# EasyEDApro.net
KiCad netlist of a schematic drawn in EasyEDA Pro
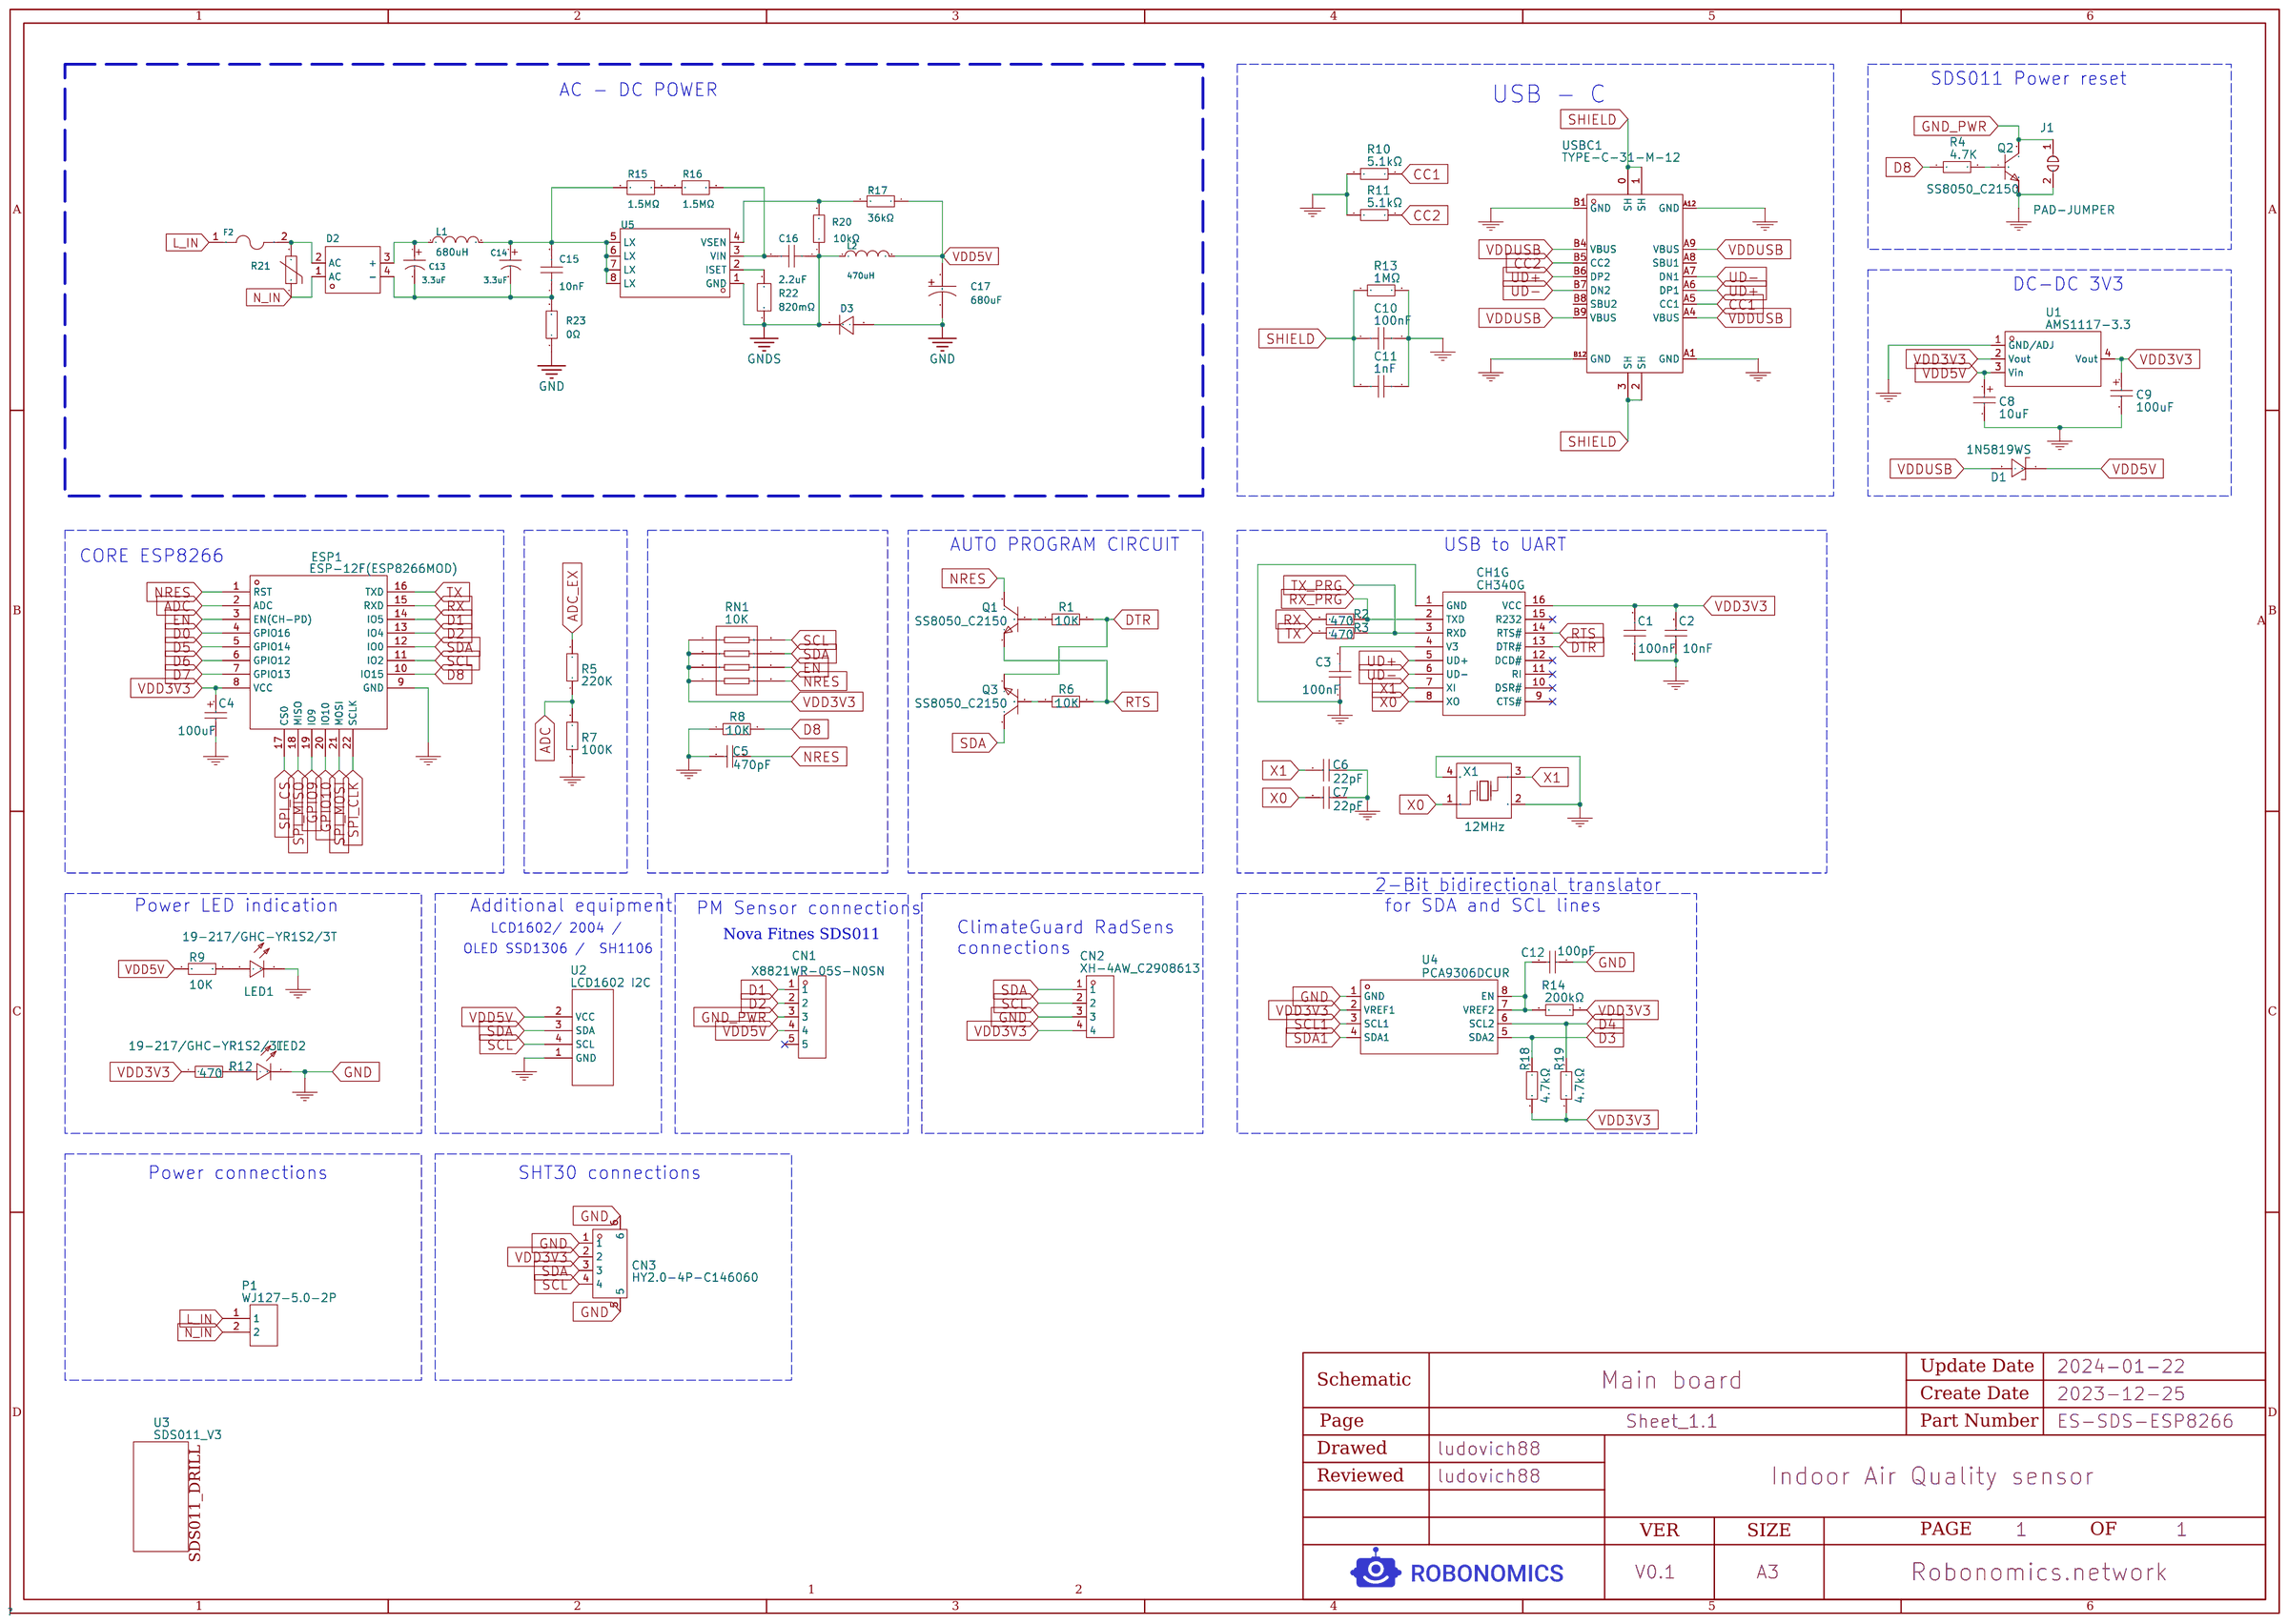
[diagram p0: schematic sheet]

(export (version "E")
  (design (tool "Eeschema 10.0.6"))
  (components
    (comp (ref "C1")
      (value "100nF")
      (footprint "easyedapro:C0603")
      (fields (field (name "Manufacturer Part") "CC0603KRX7R9BB104") (field (name "Manufacturer") "YAGEO"))
      (libsource (lib "easyedapro") (part "100nF"))
    )
    (comp (ref "C2")
      (value "10nF")
      (footprint "easyedapro:C0603")
      (fields (field (name "Manufacturer Part") "0603B103K500NT") (field (name "Manufacturer") "FH"))
      (libsource (lib "easyedapro") (part "10nF"))
    )
    (comp (ref "C3")
      (value "100nF")
      (footprint "easyedapro:C0603")
      (fields (field (name "Manufacturer Part") "CC0603KRX7R9BB104") (field (name "Manufacturer") "YAGEO"))
      (libsource (lib "easyedapro") (part "100nF"))
    )
    (comp (ref "C4")
      (value "100uF")
      (footprint "easyedapro:CAP-SMD_L3.5-W2.8")
      (fields (field (name "Manufacturer Part") "TAJB107K006RNJ") (field (name "Manufacturer") "AVX"))
      (libsource (lib "easyedapro") (part "100uF"))
    )
    (comp (ref "C5")
      (value "470pF")
      (footprint "easyedapro:C0603")
      (fields (field (name "Manufacturer Part") "0603B471K500NT") (field (name "Manufacturer") "FH"))
      (libsource (lib "easyedapro") (part "470pF"))
    )
    (comp (ref "C6")
      (value "22pF")
      (footprint "easyedapro:C0603")
      (fields (field (name "Manufacturer Part") "CL10C220JB8NNNC") (field (name "Manufacturer") "SAMSUNG"))
      (libsource (lib "easyedapro") (part "22pF"))
    )
    (comp (ref "C7")
      (value "22pF")
      (footprint "easyedapro:C0603")
      (fields (field (name "Manufacturer Part") "CL10C220JB8NNNC") (field (name "Manufacturer") "SAMSUNG"))
      (libsource (lib "easyedapro") (part "22pF"))
    )
    (comp (ref "C8")
      (value "10uF")
      (footprint "easyedapro:CAP-SMD_L3.2-W1.6-R-RD")
      (fields (field (name "Manufacturer Part") "CA45-A010M106T") (field (name "Manufacturer") "Xiangyee"))
      (libsource (lib "easyedapro") (part "10uF"))
    )
    (comp (ref "C9")
      (value "100uF")
      (footprint "easyedapro:CAP-SMD_L3.5-W2.8")
      (fields (field (name "Manufacturer Part") "TAJB107K006RNJ") (field (name "Manufacturer") "AVX"))
      (libsource (lib "easyedapro") (part "100uF"))
    )
    (comp (ref "C10")
      (value "100nF")
      (footprint "easyedapro:C0603")
      (fields (field (name "Manufacturer Part") "CC0603KRX7R9BB104") (field (name "Manufacturer") "YAGEO"))
      (libsource (lib "easyedapro") (part "100nF"))
    )
    (comp (ref "C11")
      (value "1nF")
      (footprint "easyedapro:C0603")
      (fields
        (field (name "Manufacturer Part") "GRM1885C1H102FA01D")
        (field (name "Manufacturer") "muRata(村田)")
      )
      (libsource (lib "easyedapro") (part "1nF"))
    )
    (comp (ref "C12")
      (value "100pF")
      (footprint "easyedapro:C0603")
      (fields (field (name "Manufacturer Part") "CL10C101JB8NNNC") (field (name "Manufacturer") "SAMSUNG"))
      (libsource (lib "easyedapro") (part "100pF"))
    )
    (comp (ref "C13")
      (value "3.3uF")
      (footprint "easyedapro:CAP-SMD_BD8.0-L8.3-W8.3-FD")
      (fields (field (name "Manufacturer Part") "UV2G3R3M0810") (field (name "Manufacturer") "HONOR(荣誉)"))
      (libsource (lib "easyedapro") (part "UV2G3R3M0810"))
    )
    (comp (ref "C14")
      (value "3.3uF")
      (footprint "easyedapro:CAP-SMD_BD8.0-L8.3-W8.3-FD")
      (fields (field (name "Manufacturer Part") "UV2G3R3M0810") (field (name "Manufacturer") "HONOR(荣誉)"))
      (libsource (lib "easyedapro") (part "UV2G3R3M0810"))
    )
    (comp (ref "C15")
      (value "10nF")
      (footprint "easyedapro:C1206")
      (fields (field (name "Manufacturer Part") "1206B103K102CT") (field (name "Manufacturer") "Walsin(华新科)"))
      (libsource (lib "easyedapro") (part "1206B103K102"))
    )
    (comp (ref "C16")
      (value "2.2uF")
      (footprint "easyedapro:C0805")
      (fields
        (field (name "Manufacturer Part") "CL21A225KBQNNNE")
        (field (name "Manufacturer") "SAMSUNG(三星)")
      )
      (libsource (lib "easyedapro") (part "CL21A225KBQNNNE"))
    )
    (comp (ref "C17")
      (value "680uF")
      (footprint "easyedapro:CAP-SMD_L7.3-W4.3")
      (fields (field (name "Manufacturer Part") "TAJE687K006RNJ") (field (name "Manufacturer") "KyoceraAVX"))
      (libsource (lib "easyedapro") (part "TAJE687K006RNJ"))
    )
    (comp (ref "CH1G")
      (value "CH340G")
      (footprint "easyedapro:SOIC-16_150MIL")
      (fields (field (name "Manufacturer") "WCH"))
      (libsource (lib "easyedapro") (part "CH340G"))
    )
    (comp (ref "CN1")
      (value "X8821WR-05S-N0SN")
      (footprint "easyedapro:CONN-TH_5P-P2.50_X8821WR-05S-N0SN")
      (fields (field (name "Manufacturer") "XKBConnectivity(中国星坤)"))
      (libsource (lib "easyedapro") (part "X8821WR-05S-N0SN"))
    )
    (comp (ref "CN2")
      (value "XH-4AW_C2908613")
      (footprint "easyedapro:CONN-TH_XH-4AW")
      (fields (field (name "Manufacturer Part") "XH-4AW") (field (name "Manufacturer") "HCTL(华灿天禄)"))
      (libsource (lib "easyedapro") (part "XH-4AW_C2908613"))
    )
    (comp (ref "CN3")
      (value "HY2.0-4P-C146060")
      (footprint "easyedapro:CONN-SMD_HY2.0-4P")
      (fields (field (name "Manufacturer Part") "HY-4P卧贴") (field (name "Manufacturer") "BOOMELE(博穆精密)"))
      (libsource (lib "easyedapro") (part "HY2.0-4P-C146060"))
    )
    (comp (ref "D1")
      (value "1N5819WS")
      (footprint "easyedapro:SOD-323_L1.8-W1.3-LS2.5-RD")
      (fields (field (name "Manufacturer") "GuangdongHottech"))
      (libsource (lib "easyedapro") (part "1N5819WS"))
    )
    (comp (ref "D2")
      (value "MB10F")
      (footprint "easyedapro:MBF_L4.8-W3.9-P2.50-LS6.7-BL")
      (fields (field (name "Manufacturer") "BORN(伯恩半导体)"))
      (libsource (lib "easyedapro") (part "MB10F_C306850"))
    )
    (comp (ref "D3")
      (value "ES1J")
      (footprint "easyedapro:SMA_L4.3-W2.6-LS5.2-RD")
      (fields (field (name "Manufacturer") "晶导微电子"))
      (libsource (lib "easyedapro") (part "ES1J_C115404"))
    )
    (comp (ref "ESP1")
      (value "ESP-12F(ESP8266MOD)")
      (footprint "easyedapro:WIFIM-SMD_ESP-12F-ESP8266MOD")
      (fields (field (name "Manufacturer") "Ai-Thinker"))
      (libsource (lib "easyedapro") (part "ESP-12F(ESP8266MOD)"))
    )
    (comp (ref "F2")
      (value "JFC2410-1200FS")
      (footprint "easyedapro:F2410")
      (fields (field (name "Manufacturer") "JDTfuse(集电通)"))
      (libsource (lib "easyedapro") (part "JFC2410-1200FS"))
    )
    (comp (ref "J1")
      (value "PAD-JUMPER")
      (footprint "easyedapro:PAD-JUMPER-2_1")
      (libsource (lib "easyedapro") (part "PAD-JUMPER"))
    )
    (comp (ref "L1")
      (value "680uH")
      (footprint "easyedapro:IND-SMD_L6.0-W6.0")
      (fields (field (name "Manufacturer Part") "YNR6045-681M") (field (name "Manufacturer") "YJYCOIN(益嘉源)"))
      (libsource (lib "easyedapro") (part "YNR6045-681M"))
    )
    (comp (ref "L2")
      (value "470uH")
      (footprint "easyedapro:IND-SMD_L4.0-W4.0")
      (fields (field (name "Manufacturer Part") "PNLS4030-471") (field (name "Manufacturer") "DMBJ(振宝佳)"))
      (libsource (lib "easyedapro") (part "PNLS4030-471"))
    )
    (comp (ref "LED1")
      (value "19-217/GHC-YR1S2/3T")
      (footprint "easyedapro:LED0603-R-RD")
      (fields (field (name "Manufacturer") "EVERLIGHT"))
      (libsource (lib "easyedapro") (part "19-217/GHC-YR1S2/3T"))
    )
    (comp (ref "LED2")
      (value "19-217/GHC-YR1S2/3T")
      (footprint "easyedapro:LED0603-R-RD")
      (fields (field (name "Manufacturer") "EVERLIGHT"))
      (libsource (lib "easyedapro") (part "19-217/GHC-YR1S2/3T"))
    )
    (comp (ref "P1")
      (value "WJ127-5.0-2P")
      (footprint "easyedapro:CONN-TH_2P-P5.00_CPC3703CTR")
      (fields (field (name "Manufacturer") "KANGNEX(康奈克斯电气)"))
      (libsource (lib "easyedapro") (part "WJ127-5.0-2P"))
    )
    (comp (ref "Q1")
      (value "SS8050_C2150")
      (footprint "easyedapro:SOT-23-3_L2.9-W1.3-P1.90-LS2.4-BR")
      (fields (field (name "Manufacturer Part") "SS8050") (field (name "Manufacturer") "CJ"))
      (libsource (lib "") (part "SS8050_C2150_2"))
    )
    (comp (ref "Q2")
      (value "SS8050_C2150")
      (footprint "easyedapro:SOT-23-3_L2.9-W1.3-P1.90-LS2.4-BR")
      (fields (field (name "Manufacturer Part") "SS8050") (field (name "Manufacturer") "CJ"))
      (libsource (lib "easyedapro") (part "SS8050_C2150"))
    )
    (comp (ref "Q3")
      (value "SS8050_C2150")
      (footprint "easyedapro:SOT-23-3_L2.9-W1.3-P1.90-LS2.4-BR")
      (fields (field (name "Manufacturer Part") "SS8050") (field (name "Manufacturer") "CJ"))
      (libsource (lib "") (part "SS8050_C2150_1"))
    )
    (comp (ref "R1")
      (value "10K")
      (footprint "easyedapro:R0603")
      (fields (field (name "Manufacturer Part") "0603WAF1002T5E") (field (name "Manufacturer") "UniOhm"))
      (libsource (lib "easyedapro") (part "10K"))
    )
    (comp (ref "R2")
      (value "470")
      (footprint "easyedapro:R0603")
      (fields (field (name "Manufacturer Part") "0603WAF4700T5E") (field (name "Manufacturer") "UniOhm"))
      (libsource (lib "easyedapro") (part "470"))
    )
    (comp (ref "R3")
      (value "470")
      (footprint "easyedapro:R0603")
      (fields (field (name "Manufacturer Part") "0603WAF4700T5E") (field (name "Manufacturer") "UniOhm"))
      (libsource (lib "easyedapro") (part "470"))
    )
    (comp (ref "R4")
      (value "4.7K")
      (footprint "easyedapro:R0603")
      (fields (field (name "Manufacturer Part") "0603WAF4701T5E") (field (name "Manufacturer") "UniOhm"))
      (libsource (lib "easyedapro") (part "4.7K"))
    )
    (comp (ref "R5")
      (value "220K")
      (footprint "easyedapro:R0603")
      (fields (field (name "Manufacturer Part") "0603WAF2203T5E") (field (name "Manufacturer") "UniOhm"))
      (libsource (lib "easyedapro") (part "220K"))
    )
    (comp (ref "R6")
      (value "10K")
      (footprint "easyedapro:R0603")
      (fields (field (name "Manufacturer Part") "0603WAF1002T5E") (field (name "Manufacturer") "UniOhm"))
      (libsource (lib "easyedapro") (part "10K"))
    )
    (comp (ref "R7")
      (value "100K")
      (footprint "easyedapro:R0603")
      (fields (field (name "Manufacturer Part") "0603WAF1003T5E") (field (name "Manufacturer") "UniOhm"))
      (libsource (lib "easyedapro") (part "100K"))
    )
    (comp (ref "R8")
      (value "10K")
      (footprint "easyedapro:R0603")
      (fields (field (name "Manufacturer Part") "0603WAF1002T5E") (field (name "Manufacturer") "UniOhm"))
      (libsource (lib "easyedapro") (part "10K"))
    )
    (comp (ref "R9")
      (value "10K")
      (footprint "easyedapro:R0603")
      (fields (field (name "Manufacturer Part") "0603WAF1002T5E") (field (name "Manufacturer") "UniOhm"))
      (libsource (lib "easyedapro") (part "10K"))
    )
    (comp (ref "R10")
      (value "5.1kΩ")
      (footprint "easyedapro:R0603")
      (fields
        (field (name "Manufacturer Part") "0603WAF5101T5E")
        (field (name "Manufacturer") "UNI-ROYAL(厚声)")
      )
      (libsource (lib "easyedapro") (part "5.1kΩ"))
    )
    (comp (ref "R11")
      (value "5.1kΩ")
      (footprint "easyedapro:R0603")
      (fields
        (field (name "Manufacturer Part") "0603WAF5101T5E")
        (field (name "Manufacturer") "UNI-ROYAL(厚声)")
      )
      (libsource (lib "easyedapro") (part "5.1kΩ"))
    )
    (comp (ref "R12")
      (value "470")
      (footprint "easyedapro:R0603")
      (fields (field (name "Manufacturer Part") "0603WAF4700T5E") (field (name "Manufacturer") "UniOhm"))
      (libsource (lib "easyedapro") (part "470"))
    )
    (comp (ref "R13")
      (value "1MΩ")
      (footprint "easyedapro:R0603")
      (fields
        (field (name "Manufacturer Part") "0603WAF1004T5E")
        (field (name "Manufacturer") "UNI-ROYAL(厚声)")
      )
      (libsource (lib "easyedapro") (part "1MΩ"))
    )
    (comp (ref "R14")
      (value "200kΩ")
      (footprint "easyedapro:R0603")
      (fields (field (name "Manufacturer Part") "0603WAF2003T5E") (field (name "Manufacturer") "UniOhm"))
      (libsource (lib "easyedapro") (part "200kΩ"))
    )
    (comp (ref "R15")
      (value "1.5MΩ")
      (footprint "easyedapro:R1206")
      (fields (field (name "Manufacturer Part") "AC1206FR-071M5L") (field (name "Manufacturer") "YAGEO(国巨)"))
      (libsource (lib "easyedapro") (part "AC1206FR-071M5L"))
    )
    (comp (ref "R16")
      (value "1.5MΩ")
      (footprint "easyedapro:R1206")
      (fields (field (name "Manufacturer Part") "AC1206FR-071M5L") (field (name "Manufacturer") "YAGEO(国巨)"))
      (libsource (lib "easyedapro") (part "AC1206FR-071M5L"))
    )
    (comp (ref "R17")
      (value "36kΩ")
      (footprint "easyedapro:R0805")
      (fields
        (field (name "Manufacturer Part") "0805W8F3602T5E")
        (field (name "Manufacturer") "UNI-ROYAL(厚声)")
      )
      (libsource (lib "easyedapro") (part "0805W8F3602T5E"))
    )
    (comp (ref "R18")
      (value "4.7kΩ")
      (footprint "easyedapro:R0603")
      (fields (field (name "Manufacturer Part") "0603WAF4701T5E") (field (name "Manufacturer") "UniOhm"))
      (libsource (lib "easyedapro") (part "4.7K"))
    )
    (comp (ref "R19")
      (value "4.7kΩ")
      (footprint "easyedapro:R0603")
      (fields (field (name "Manufacturer Part") "0603WAF4701T5E") (field (name "Manufacturer") "UniOhm"))
      (libsource (lib "easyedapro") (part "4.7K"))
    )
    (comp (ref "R20")
      (value "10kΩ")
      (footprint "easyedapro:R0805")
      (fields
        (field (name "Manufacturer Part") "0805W8F1002T5E")
        (field (name "Manufacturer") "UNI-ROYAL(厚声)")
      )
      (libsource (lib "easyedapro") (part "0805W8F1002T5E"))
    )
    (comp (ref "R21")
      (value "07D471K68RV0149")
      (footprint "easyedapro:RES-SMD_L8.2-W6.3")
      (fields (field (name "Manufacturer") "KNSCHA(科尼盛)"))
      (libsource (lib "easyedapro") (part "07D471K68RV0149"))
    )
    (comp (ref "R22")
      (value "820mΩ")
      (footprint "easyedapro:R0805")
      (fields
        (field (name "Manufacturer Part") "0805W8F820LT5E")
        (field (name "Manufacturer") "UNI-ROYAL(厚声)")
      )
      (libsource (lib "easyedapro") (part "RT0805BRD071RL"))
    )
    (comp (ref "R23")
      (value "0Ω")
      (footprint "easyedapro:R0805")
      (fields
        (field (name "Manufacturer Part") "0805W8J0000T5E")
        (field (name "Manufacturer") "UNI-ROYAL(厚声)")
      )
      (libsource (lib "easyedapro") (part "0805W8J0000T5E"))
    )
    (comp (ref "RN1")
      (value "10K")
      (footprint "easyedapro:RES-ARRAY-SMD_0603-8P-L3.2-W1.6-BL")
      (fields (field (name "Manufacturer Part") "4D03WGJ0103T5E") (field (name "Manufacturer") "UniOhm"))
      (libsource (lib "") (part "10K_1"))
    )
    (comp (ref "U1")
      (value "AMS1117-3.3")
      (footprint "easyedapro:SOT-223-3_L6.5-W3.4-P2.30-LS7.0-BR")
      (fields (field (name "Manufacturer") "AMS"))
      (libsource (lib "easyedapro") (part "AMS1117-3.3"))
    )
    (comp (ref "U2")
      (value "LCD1602 I2C")
      (footprint "easyedapro:LCD1620 I2C")
      (fields (field (name "Manufacturer Part") "LCD1602I2C"))
      (libsource (lib "easyedapro") (part "LCD1602 I2C"))
    )
    (comp (ref "U3")
      (value "SDS011_V3")
      (footprint "easyedapro:SDS011_V3")
      (libsource (lib "easyedapro") (part "SDS011_V3"))
    )
    (comp (ref "U4")
      (value "PCA9306DCUR")
      (footprint "easyedapro:SSOP-8_L2.0-W2.3-P0.50-LS3.1-BR")
      (fields (field (name "Manufacturer") "TI"))
      (libsource (lib "easyedapro") (part "PCA9306DCUR"))
    )
    (comp (ref "U5")
      (value "SY50282FAC")
      (footprint "easyedapro:SOIC-8_L4.9-W3.9-P1.27-LS6.0-BL")
      (fields (field (name "Manufacturer") "silergy(矽力杰)"))
      (libsource (lib "easyedapro") (part "SY50282FAC"))
    )
    (comp (ref "USBC1")
      (value "TYPE-C-31-M-12")
      (footprint "easyedapro:USB-C_SMD-TYPE-C-31-M-12")
      (fields
        (field (name "Manufacturer Part") "KH-TYPE-C-16P")
        (field (name "Manufacturer") "kinghelm(金航标)")
      )
      (libsource (lib "easyedapro") (part "TYPE-C-31-M-12"))
    )
    (comp (ref "X1")
      (value "12MHz")
      (footprint "easyedapro:OSC-SMD_4P-L3.2-W2.5-BL")
      (fields (field (name "Manufacturer Part") "X322512MSB4SI") (field (name "Manufacturer") "YXC"))
      (libsource (lib "easyedapro") (part "12MHz"))
    )
  )
  (nets
    (net (code "1") (name "ADC") (class "Default")
      (node (ref "ESP1") (pin "2") (pinfunction "ADC_2") (pintype "input"))
      (node (ref "R5") (pin "1") (pinfunction "1_1") (pintype "input"))
      (node (ref "R7") (pin "2") (pinfunction "2_2") (pintype "input"))
    )
    (net (code "2") (name "ADC_EX") (class "Default")
      (node (ref "R5") (pin "2") (pinfunction "2_2") (pintype "input"))
    )
    (net (code "3") (name "CC1") (class "Default")
      (node (ref "R10") (pin "2") (pinfunction "2_2") (pintype "input"))
      (node (ref "USBC1") (pin "A5") (pinfunction "CC1_A5") (pintype "input"))
    )
    (net (code "4") (name "CC2") (class "Default")
      (node (ref "R11") (pin "2") (pinfunction "2_2") (pintype "input"))
      (node (ref "USBC1") (pin "B5") (pinfunction "CC2_B5") (pintype "input"))
    )
    (net (code "5") (name "D0") (class "Default")
      (node (ref "ESP1") (pin "4") (pinfunction "GPIO16_4") (pintype "input"))
    )
    (net (code "6") (name "D1") (class "Default")
      (node (ref "CN1") (pin "1") (pinfunction "1_1") (pintype "input"))
      (node (ref "ESP1") (pin "14") (pinfunction "IO5_14") (pintype "input"))
    )
    (net (code "7") (name "D2") (class "Default")
      (node (ref "CN1") (pin "2") (pinfunction "2_2") (pintype "input"))
      (node (ref "ESP1") (pin "13") (pinfunction "IO4_13") (pintype "input"))
    )
    (net (code "8") (name "D3") (class "Default")
      (node (ref "R18") (pin "1") (pinfunction "1_1") (pintype "input"))
      (node (ref "U4") (pin "5") (pinfunction "SDA2_5") (pintype "input"))
    )
    (net (code "9") (name "D4") (class "Default")
      (node (ref "R19") (pin "1") (pinfunction "1_1") (pintype "input"))
      (node (ref "U4") (pin "6") (pinfunction "SCL2_6") (pintype "input"))
    )
    (net (code "10") (name "D5") (class "Default")
      (node (ref "ESP1") (pin "5") (pinfunction "GPIO14_5") (pintype "input"))
    )
    (net (code "11") (name "D6") (class "Default")
      (node (ref "ESP1") (pin "6") (pinfunction "GPIO12_6") (pintype "input"))
    )
    (net (code "12") (name "D7") (class "Default")
      (node (ref "ESP1") (pin "7") (pinfunction "GPIO13_7") (pintype "input"))
    )
    (net (code "13") (name "D8") (class "Default")
      (node (ref "ESP1") (pin "10") (pinfunction "IO15_10") (pintype "input"))
      (node (ref "R4") (pin "1") (pinfunction "1_1") (pintype "input"))
      (node (ref "R8") (pin "2") (pinfunction "2_2") (pintype "input"))
    )
    (net (code "14") (name "DTR") (class "Default")
      (node (ref "CH1G") (pin "13") (pinfunction "DTR#_13") (pintype "input"))
      (node (ref "Q3") (pin "2") (pinfunction "E_2") (pintype "input"))
      (node (ref "R1") (pin "2") (pinfunction "2_2") (pintype "input"))
    )
    (net (code "15") (name "EN") (class "Default")
      (node (ref "ESP1") (pin "3") (pinfunction "EN(CH-PD)_3") (pintype "input"))
      (node (ref "RN1") (pin "6") (pinfunction "6_6") (pintype "input"))
    )
    (net (code "16") (name "GND") (class "Default")
      (node (ref "C1") (pin "1") (pinfunction "1_1") (pintype "input"))
      (node (ref "C10") (pin "2") (pinfunction "2_2") (pintype "input"))
      (node (ref "C11") (pin "2") (pinfunction "2_2") (pintype "input"))
      (node (ref "C12") (pin "1") (pinfunction "1_1") (pintype "input"))
      (node (ref "C17") (pin "2") (pinfunction "2_2") (pintype "input"))
      (node (ref "C2") (pin "1") (pinfunction "1_1") (pintype "input"))
      (node (ref "C3") (pin "1") (pinfunction "1_1") (pintype "input"))
      (node (ref "C4") (pin "2") (pinfunction "2_2") (pintype "input"))
      (node (ref "C5") (pin "1") (pinfunction "1_1") (pintype "input"))
      (node (ref "C6") (pin "1") (pinfunction "1_1") (pintype "input"))
      (node (ref "C7") (pin "1") (pinfunction "1_1") (pintype "input"))
      (node (ref "C8") (pin "1") (pinfunction "1_1") (pintype "input"))
      (node (ref "C9") (pin "2") (pinfunction "2_2") (pintype "input"))
      (node (ref "CH1G") (pin "1") (pinfunction "GND_1") (pintype "input"))
      (node (ref "CN2") (pin "3") (pinfunction "3_3") (pintype "input"))
      (node (ref "CN3") (pin "1") (pinfunction "1_1") (pintype "input"))
      (node (ref "CN3") (pin "5") (pinfunction "5_5") (pintype "input"))
      (node (ref "CN3") (pin "6") (pinfunction "6_6") (pintype "input"))
      (node (ref "D3") (pin "2") (pinfunction "A_2") (pintype "input"))
      (node (ref "ESP1") (pin "9") (pinfunction "GND_9") (pintype "input"))
      (node (ref "J1") (pin "2") (pinfunction "B_2") (pintype "input"))
      (node (ref "LED1") (pin "2") (pinfunction "C_2") (pintype "input"))
      (node (ref "LED2") (pin "2") (pinfunction "C_2") (pintype "input"))
      (node (ref "Q2") (pin "2") (pinfunction "E_2") (pintype "input"))
      (node (ref "R10") (pin "1") (pinfunction "1_1") (pintype "input"))
      (node (ref "R11") (pin "1") (pinfunction "1_1") (pintype "input"))
      (node (ref "R13") (pin "2") (pinfunction "2_2") (pintype "input"))
      (node (ref "R23") (pin "1") (pinfunction "1_1") (pintype "input"))
      (node (ref "R7") (pin "1") (pinfunction "1_1") (pintype "input"))
      (node (ref "R8") (pin "1") (pinfunction "1_1") (pintype "input"))
      (node (ref "U1") (pin "1") (pinfunction "GND/ADJ_1") (pintype "input"))
      (node (ref "U2") (pin "1") (pinfunction "GND_1") (pintype "input"))
      (node (ref "U4") (pin "1") (pinfunction "GND_1") (pintype "input"))
      (node (ref "USBC1") (pin "A1") (pinfunction "GND_A1") (pintype "input"))
      (node (ref "USBC1") (pin "A12") (pinfunction "GND_A12") (pintype "input"))
      (node (ref "USBC1") (pin "B1") (pinfunction "GND_B1") (pintype "input"))
      (node (ref "USBC1") (pin "B12") (pinfunction "GND_B12") (pintype "input"))
      (node (ref "X1") (pin "2") (pinfunction "GND_2") (pintype "input"))
      (node (ref "X1") (pin "4") (pinfunction "GND_4") (pintype "input"))
    )
    (net (code "17") (name "GNDS") (class "Default")
      (node (ref "C16") (pin "1") (pinfunction "1_1") (pintype "input"))
      (node (ref "D3") (pin "1") (pinfunction "C_1") (pintype "input"))
      (node (ref "L2") (pin "1") (pinfunction "1_1") (pintype "input"))
      (node (ref "R20") (pin "1") (pinfunction "1_1") (pintype "input"))
      (node (ref "R22") (pin "1") (pinfunction "1_1") (pintype "input"))
      (node (ref "U5") (pin "1") (pinfunction "GND_1") (pintype "input"))
    )
    (net (code "18") (name "GND_PWR") (class "Default")
      (node (ref "CN1") (pin "3") (pinfunction "3_3") (pintype "input"))
      (node (ref "J1") (pin "1") (pinfunction "A_1") (pintype "input"))
      (node (ref "Q2") (pin "3") (pinfunction "C_3") (pintype "input"))
    )
    (net (code "19") (name "GPIO9") (class "Default")
      (node (ref "ESP1") (pin "19") (pinfunction "IO9_19") (pintype "input"))
    )
    (net (code "20") (name "GPIO10") (class "Default")
      (node (ref "ESP1") (pin "20") (pinfunction "IO10_20") (pintype "input"))
    )
    (net (code "21") (name "L_IN") (class "Default")
      (node (ref "F2") (pin "1") (pinfunction "1_1") (pintype "input"))
      (node (ref "P1") (pin "1") (pinfunction "1_1") (pintype "input"))
    )
    (net (code "22") (name "NRES") (class "Default")
      (node (ref "C5") (pin "2") (pinfunction "2_2") (pintype "input"))
      (node (ref "ESP1") (pin "1") (pinfunction "RST_1") (pintype "input"))
      (node (ref "Q1") (pin "3") (pinfunction "C_3") (pintype "input"))
      (node (ref "RN1") (pin "5") (pinfunction "5_5") (pintype "input"))
    )
    (net (code "23") (name "N_IN") (class "Default")
      (node (ref "D2") (pin "1") (pinfunction "AC_1") (pintype "input"))
      (node (ref "P1") (pin "2") (pinfunction "2_2") (pintype "input"))
      (node (ref "R21") (pin "1") (pinfunction "1_1") (pintype "input"))
    )
    (net (code "24") (name "Net-(C14-Pad1)") (class "Default")
      (node (ref "C14") (pin "1") (pinfunction "1_1") (pintype "input"))
      (node (ref "C15") (pin "2") (pinfunction "2_2") (pintype "input"))
      (node (ref "L1") (pin "2") (pinfunction "2_2") (pintype "input"))
      (node (ref "R15") (pin "1") (pinfunction "1_1") (pintype "input"))
      (node (ref "U5") (pin "5") (pinfunction "LX_5") (pintype "input"))
      (node (ref "U5") (pin "6") (pinfunction "LX_6") (pintype "input"))
      (node (ref "U5") (pin "7") (pinfunction "LX_7") (pintype "input"))
      (node (ref "U5") (pin "8") (pinfunction "LX_8") (pintype "input"))
    )
    (net (code "25") (name "Net-(CH1G-V3)") (class "Default")
      (node (ref "C3") (pin "2") (pinfunction "2_2") (pintype "input"))
      (node (ref "CH1G") (pin "4") (pinfunction "V3_4") (pintype "input"))
    )
    (net (code "26") (name "Net-(D2-+)") (class "Default")
      (node (ref "C13") (pin "1") (pinfunction "1_1") (pintype "input"))
      (node (ref "D2") (pin "3") (pinfunction "+_3") (pintype "input"))
      (node (ref "L1") (pin "1") (pinfunction "1_1") (pintype "input"))
    )
    (net (code "27") (name "Net-(D2--)") (class "Default")
      (node (ref "C13") (pin "2") (pinfunction "2_2") (pintype "input"))
      (node (ref "C14") (pin "2") (pinfunction "2_2") (pintype "input"))
      (node (ref "C15") (pin "1") (pinfunction "1_1") (pintype "input"))
      (node (ref "D2") (pin "4") (pinfunction "-_4") (pintype "input"))
      (node (ref "R23") (pin "2") (pinfunction "2_2") (pintype "input"))
    )
    (net (code "28") (name "Net-(D2-AC-Pad2)") (class "Default")
      (node (ref "D2") (pin "2") (pinfunction "AC_2") (pintype "input"))
      (node (ref "F2") (pin "2") (pinfunction "2_2") (pintype "input"))
      (node (ref "R21") (pin "2") (pinfunction "2_2") (pintype "input"))
    )
    (net (code "29") (name "Net-(LED1-A)") (class "Default")
      (node (ref "LED1") (pin "1") (pinfunction "A_1") (pintype "input"))
      (node (ref "R9") (pin "2") (pinfunction "2_2") (pintype "input"))
    )
    (net (code "30") (name "Net-(LED2-A)") (class "Default")
      (node (ref "LED2") (pin "1") (pinfunction "A_1") (pintype "input"))
      (node (ref "R12") (pin "2") (pinfunction "2_2") (pintype "input"))
    )
    (net (code "31") (name "Net-(Q1-B)") (class "Default")
      (node (ref "Q1") (pin "1") (pinfunction "B_1") (pintype "input"))
      (node (ref "R1") (pin "1") (pinfunction "1_1") (pintype "input"))
    )
    (net (code "32") (name "Net-(Q2-B)") (class "Default")
      (node (ref "Q2") (pin "1") (pinfunction "B_1") (pintype "input"))
      (node (ref "R4") (pin "2") (pinfunction "2_2") (pintype "input"))
    )
    (net (code "33") (name "Net-(Q3-B)") (class "Default")
      (node (ref "Q3") (pin "1") (pinfunction "B_1") (pintype "input"))
      (node (ref "R6") (pin "1") (pinfunction "1_1") (pintype "input"))
    )
    (net (code "34") (name "Net-(R15-Pad2)") (class "Default")
      (node (ref "R15") (pin "2") (pinfunction "2_2") (pintype "input"))
      (node (ref "R16") (pin "1") (pinfunction "1_1") (pintype "input"))
    )
    (net (code "35") (name "Net-(U4-EN)") (class "Default")
      (node (ref "C12") (pin "2") (pinfunction "2_2") (pintype "input"))
      (node (ref "R14") (pin "1") (pinfunction "1_1") (pintype "input"))
      (node (ref "U4") (pin "7") (pinfunction "VREF2_7") (pintype "input"))
      (node (ref "U4") (pin "8") (pinfunction "EN_8") (pintype "input"))
    )
    (net (code "36") (name "Net-(U5-ISET)") (class "Default")
      (node (ref "R22") (pin "2") (pinfunction "2_2") (pintype "input"))
      (node (ref "U5") (pin "2") (pinfunction "ISET_2") (pintype "input"))
    )
    (net (code "37") (name "Net-(U5-VIN)") (class "Default")
      (node (ref "C16") (pin "2") (pinfunction "2_2") (pintype "input"))
      (node (ref "R16") (pin "2") (pinfunction "2_2") (pintype "input"))
      (node (ref "U5") (pin "3") (pinfunction "VIN_3") (pintype "input"))
    )
    (net (code "38") (name "Net-(U5-VSEN)") (class "Default")
      (node (ref "R17") (pin "2") (pinfunction "2_2") (pintype "input"))
      (node (ref "R20") (pin "2") (pinfunction "2_2") (pintype "input"))
      (node (ref "U5") (pin "4") (pinfunction "VSEN_4") (pintype "input"))
    )
    (net (code "39") (name "RTS") (class "Default")
      (node (ref "CH1G") (pin "14") (pinfunction "RTS#_14") (pintype "input"))
      (node (ref "Q1") (pin "2") (pinfunction "E_2") (pintype "input"))
      (node (ref "R6") (pin "2") (pinfunction "2_2") (pintype "input"))
    )
    (net (code "40") (name "RX") (class "Default")
      (node (ref "ESP1") (pin "15") (pinfunction "RXD_15") (pintype "input"))
      (node (ref "R2") (pin "1") (pinfunction "1_1") (pintype "input"))
    )
    (net (code "41") (name "RX_PRG") (class "Default")
      (node (ref "CH1G") (pin "2") (pinfunction "TXD_2") (pintype "input"))
      (node (ref "R2") (pin "2") (pinfunction "2_2") (pintype "input"))
    )
    (net (code "42") (name "SCL") (class "Default")
      (node (ref "CN2") (pin "2") (pinfunction "2_2") (pintype "input"))
      (node (ref "CN3") (pin "4") (pinfunction "4_4") (pintype "input"))
      (node (ref "ESP1") (pin "11") (pinfunction "IO2_11") (pintype "input"))
      (node (ref "RN1") (pin "8") (pinfunction "8_8") (pintype "input"))
      (node (ref "U2") (pin "4") (pinfunction "SCL_4") (pintype "input"))
    )
    (net (code "43") (name "SCL1") (class "Default")
      (node (ref "U4") (pin "3") (pinfunction "SCL1_3") (pintype "input"))
    )
    (net (code "44") (name "SDA") (class "Default")
      (node (ref "CN2") (pin "1") (pinfunction "1_1") (pintype "input"))
      (node (ref "CN3") (pin "3") (pinfunction "3_3") (pintype "input"))
      (node (ref "ESP1") (pin "12") (pinfunction "IO0_12") (pintype "input"))
      (node (ref "Q3") (pin "3") (pinfunction "C_3") (pintype "input"))
      (node (ref "RN1") (pin "7") (pinfunction "7_7") (pintype "input"))
      (node (ref "U2") (pin "3") (pinfunction "SDA_3") (pintype "input"))
    )
    (net (code "45") (name "SDA1") (class "Default")
      (node (ref "U4") (pin "4") (pinfunction "SDA1_4") (pintype "input"))
    )
    (net (code "46") (name "SHIELD") (class "Default")
      (node (ref "C10") (pin "1") (pinfunction "1_1") (pintype "input"))
      (node (ref "C11") (pin "1") (pinfunction "1_1") (pintype "input"))
      (node (ref "R13") (pin "1") (pinfunction "1_1") (pintype "input"))
      (node (ref "USBC1") (pin "0") (pinfunction "SH_0") (pintype "input"))
      (node (ref "USBC1") (pin "1") (pinfunction "SH_1") (pintype "input"))
      (node (ref "USBC1") (pin "2") (pinfunction "SH_2") (pintype "input"))
      (node (ref "USBC1") (pin "3") (pinfunction "SH_3") (pintype "input"))
    )
    (net (code "47") (name "SPI_CLK") (class "Default")
      (node (ref "ESP1") (pin "22") (pinfunction "SCLK_22") (pintype "input"))
    )
    (net (code "48") (name "SPI_CS") (class "Default")
      (node (ref "ESP1") (pin "17") (pinfunction "CS0_17") (pintype "input"))
    )
    (net (code "49") (name "SPI_MISO") (class "Default")
      (node (ref "ESP1") (pin "18") (pinfunction "MISO_18") (pintype "input"))
    )
    (net (code "50") (name "SPI_MOSI") (class "Default")
      (node (ref "ESP1") (pin "21") (pinfunction "MOSI_21") (pintype "input"))
    )
    (net (code "51") (name "TX") (class "Default")
      (node (ref "ESP1") (pin "16") (pinfunction "TXD_16") (pintype "input"))
      (node (ref "R3") (pin "1") (pinfunction "1_1") (pintype "input"))
    )
    (net (code "52") (name "TX_PRG") (class "Default")
      (node (ref "CH1G") (pin "3") (pinfunction "RXD_3") (pintype "input"))
      (node (ref "R3") (pin "2") (pinfunction "2_2") (pintype "input"))
    )
    (net (code "53") (name "UD+") (class "Default")
      (node (ref "CH1G") (pin "5") (pinfunction "UD+_5") (pintype "input"))
      (node (ref "USBC1") (pin "A6") (pinfunction "DP1_A6") (pintype "input"))
      (node (ref "USBC1") (pin "B6") (pinfunction "DP2_B6") (pintype "input"))
    )
    (net (code "54") (name "UD-") (class "Default")
      (node (ref "CH1G") (pin "6") (pinfunction "UD-_6") (pintype "input"))
      (node (ref "USBC1") (pin "A7") (pinfunction "DN1_A7") (pintype "input"))
      (node (ref "USBC1") (pin "B7") (pinfunction "DN2_B7") (pintype "input"))
    )
    (net (code "55") (name "VDD3V3") (class "Default")
      (node (ref "C1") (pin "2") (pinfunction "2_2") (pintype "input"))
      (node (ref "C2") (pin "2") (pinfunction "2_2") (pintype "input"))
      (node (ref "C4") (pin "1") (pinfunction "1_1") (pintype "input"))
      (node (ref "C9") (pin "1") (pinfunction "1_1") (pintype "input"))
      (node (ref "CH1G") (pin "16") (pinfunction "VCC_16") (pintype "input"))
      (node (ref "CN2") (pin "4") (pinfunction "4_4") (pintype "input"))
      (node (ref "CN3") (pin "2") (pinfunction "2_2") (pintype "input"))
      (node (ref "ESP1") (pin "8") (pinfunction "VCC_8") (pintype "input"))
      (node (ref "R12") (pin "1") (pinfunction "1_1") (pintype "input"))
      (node (ref "R14") (pin "2") (pinfunction "2_2") (pintype "input"))
      (node (ref "R18") (pin "2") (pinfunction "2_2") (pintype "input"))
      (node (ref "R19") (pin "2") (pinfunction "2_2") (pintype "input"))
      (node (ref "RN1") (pin "1") (pinfunction "1_1") (pintype "input"))
      (node (ref "RN1") (pin "2") (pinfunction "2_2") (pintype "input"))
      (node (ref "RN1") (pin "3") (pinfunction "3_3") (pintype "input"))
      (node (ref "RN1") (pin "4") (pinfunction "4_4") (pintype "input"))
      (node (ref "U1") (pin "2") (pinfunction "Vout_2") (pintype "input"))
      (node (ref "U1") (pin "4") (pinfunction "Vout_4") (pintype "input"))
      (node (ref "U4") (pin "2") (pinfunction "VREF1_2") (pintype "input"))
    )
    (net (code "56") (name "VDD5V") (class "Default")
      (node (ref "C17") (pin "1") (pinfunction "1_1") (pintype "input"))
      (node (ref "C8") (pin "2") (pinfunction "2_2") (pintype "input"))
      (node (ref "CN1") (pin "4") (pinfunction "4_4") (pintype "input"))
      (node (ref "D1") (pin "1") (pinfunction "C_1") (pintype "input"))
      (node (ref "L2") (pin "2") (pinfunction "2_2") (pintype "input"))
      (node (ref "R17") (pin "1") (pinfunction "1_1") (pintype "input"))
      (node (ref "R9") (pin "1") (pinfunction "1_1") (pintype "input"))
      (node (ref "U1") (pin "3") (pinfunction "Vin_3") (pintype "input"))
      (node (ref "U2") (pin "2") (pinfunction "VCC_2") (pintype "input"))
    )
    (net (code "57") (name "VDDUSB") (class "Default")
      (node (ref "D1") (pin "2") (pinfunction "A_2") (pintype "input"))
      (node (ref "USBC1") (pin "A4") (pinfunction "VBUS_A4") (pintype "input"))
      (node (ref "USBC1") (pin "A9") (pinfunction "VBUS_A9") (pintype "input"))
      (node (ref "USBC1") (pin "B4") (pinfunction "VBUS_B4") (pintype "input"))
      (node (ref "USBC1") (pin "B9") (pinfunction "VBUS_B9") (pintype "input"))
    )
    (net (code "58") (name "X0") (class "Default")
      (node (ref "C7") (pin "2") (pinfunction "2_2") (pintype "input"))
      (node (ref "CH1G") (pin "8") (pinfunction "XO_8") (pintype "input"))
      (node (ref "X1") (pin "1") (pinfunction "OSC1_1") (pintype "input"))
    )
    (net (code "59") (name "X1") (class "Default")
      (node (ref "C6") (pin "2") (pinfunction "2_2") (pintype "input"))
      (node (ref "CH1G") (pin "7") (pinfunction "XI_7") (pintype "input"))
      (node (ref "X1") (pin "3") (pinfunction "OSC2_3") (pintype "input"))
    )
    (net (code "60") (name "unconnected-(CH1G-CTS#-Pad9)") (class "Default")
      (node (ref "CH1G") (pin "9") (pinfunction "CTS#_9") (pintype "input+no_connect"))
    )
    (net (code "61") (name "unconnected-(CH1G-DCD#-Pad12)") (class "Default")
      (node (ref "CH1G") (pin "12") (pinfunction "DCD#_12") (pintype "input+no_connect"))
    )
    (net (code "62") (name "unconnected-(CH1G-DSR#-Pad10)") (class "Default")
      (node (ref "CH1G") (pin "10") (pinfunction "DSR#_10") (pintype "input+no_connect"))
    )
    (net (code "63") (name "unconnected-(CH1G-R232-Pad15)") (class "Default")
      (node (ref "CH1G") (pin "15") (pinfunction "R232_15") (pintype "input+no_connect"))
    )
    (net (code "64") (name "unconnected-(CH1G-RI-Pad11)") (class "Default")
      (node (ref "CH1G") (pin "11") (pinfunction "RI_11") (pintype "input+no_connect"))
    )
    (net (code "65") (name "unconnected-(CN1-Pad5)") (class "Default")
      (node (ref "CN1") (pin "5") (pinfunction "5_5") (pintype "input+no_connect"))
    )
    (net (code "66") (name "unconnected-(USBC1-SBU1-PadA8)") (class "Default")
      (node (ref "USBC1") (pin "A8") (pinfunction "SBU1_A8") (pintype "input"))
    )
    (net (code "67") (name "unconnected-(USBC1-SBU2-PadB8)") (class "Default")
      (node (ref "USBC1") (pin "B8") (pinfunction "SBU2_B8") (pintype "input"))
    )
  )
)
